# LAN9254_D_P2.net
KiCad netlist of a schematic drawn in Altium Designer
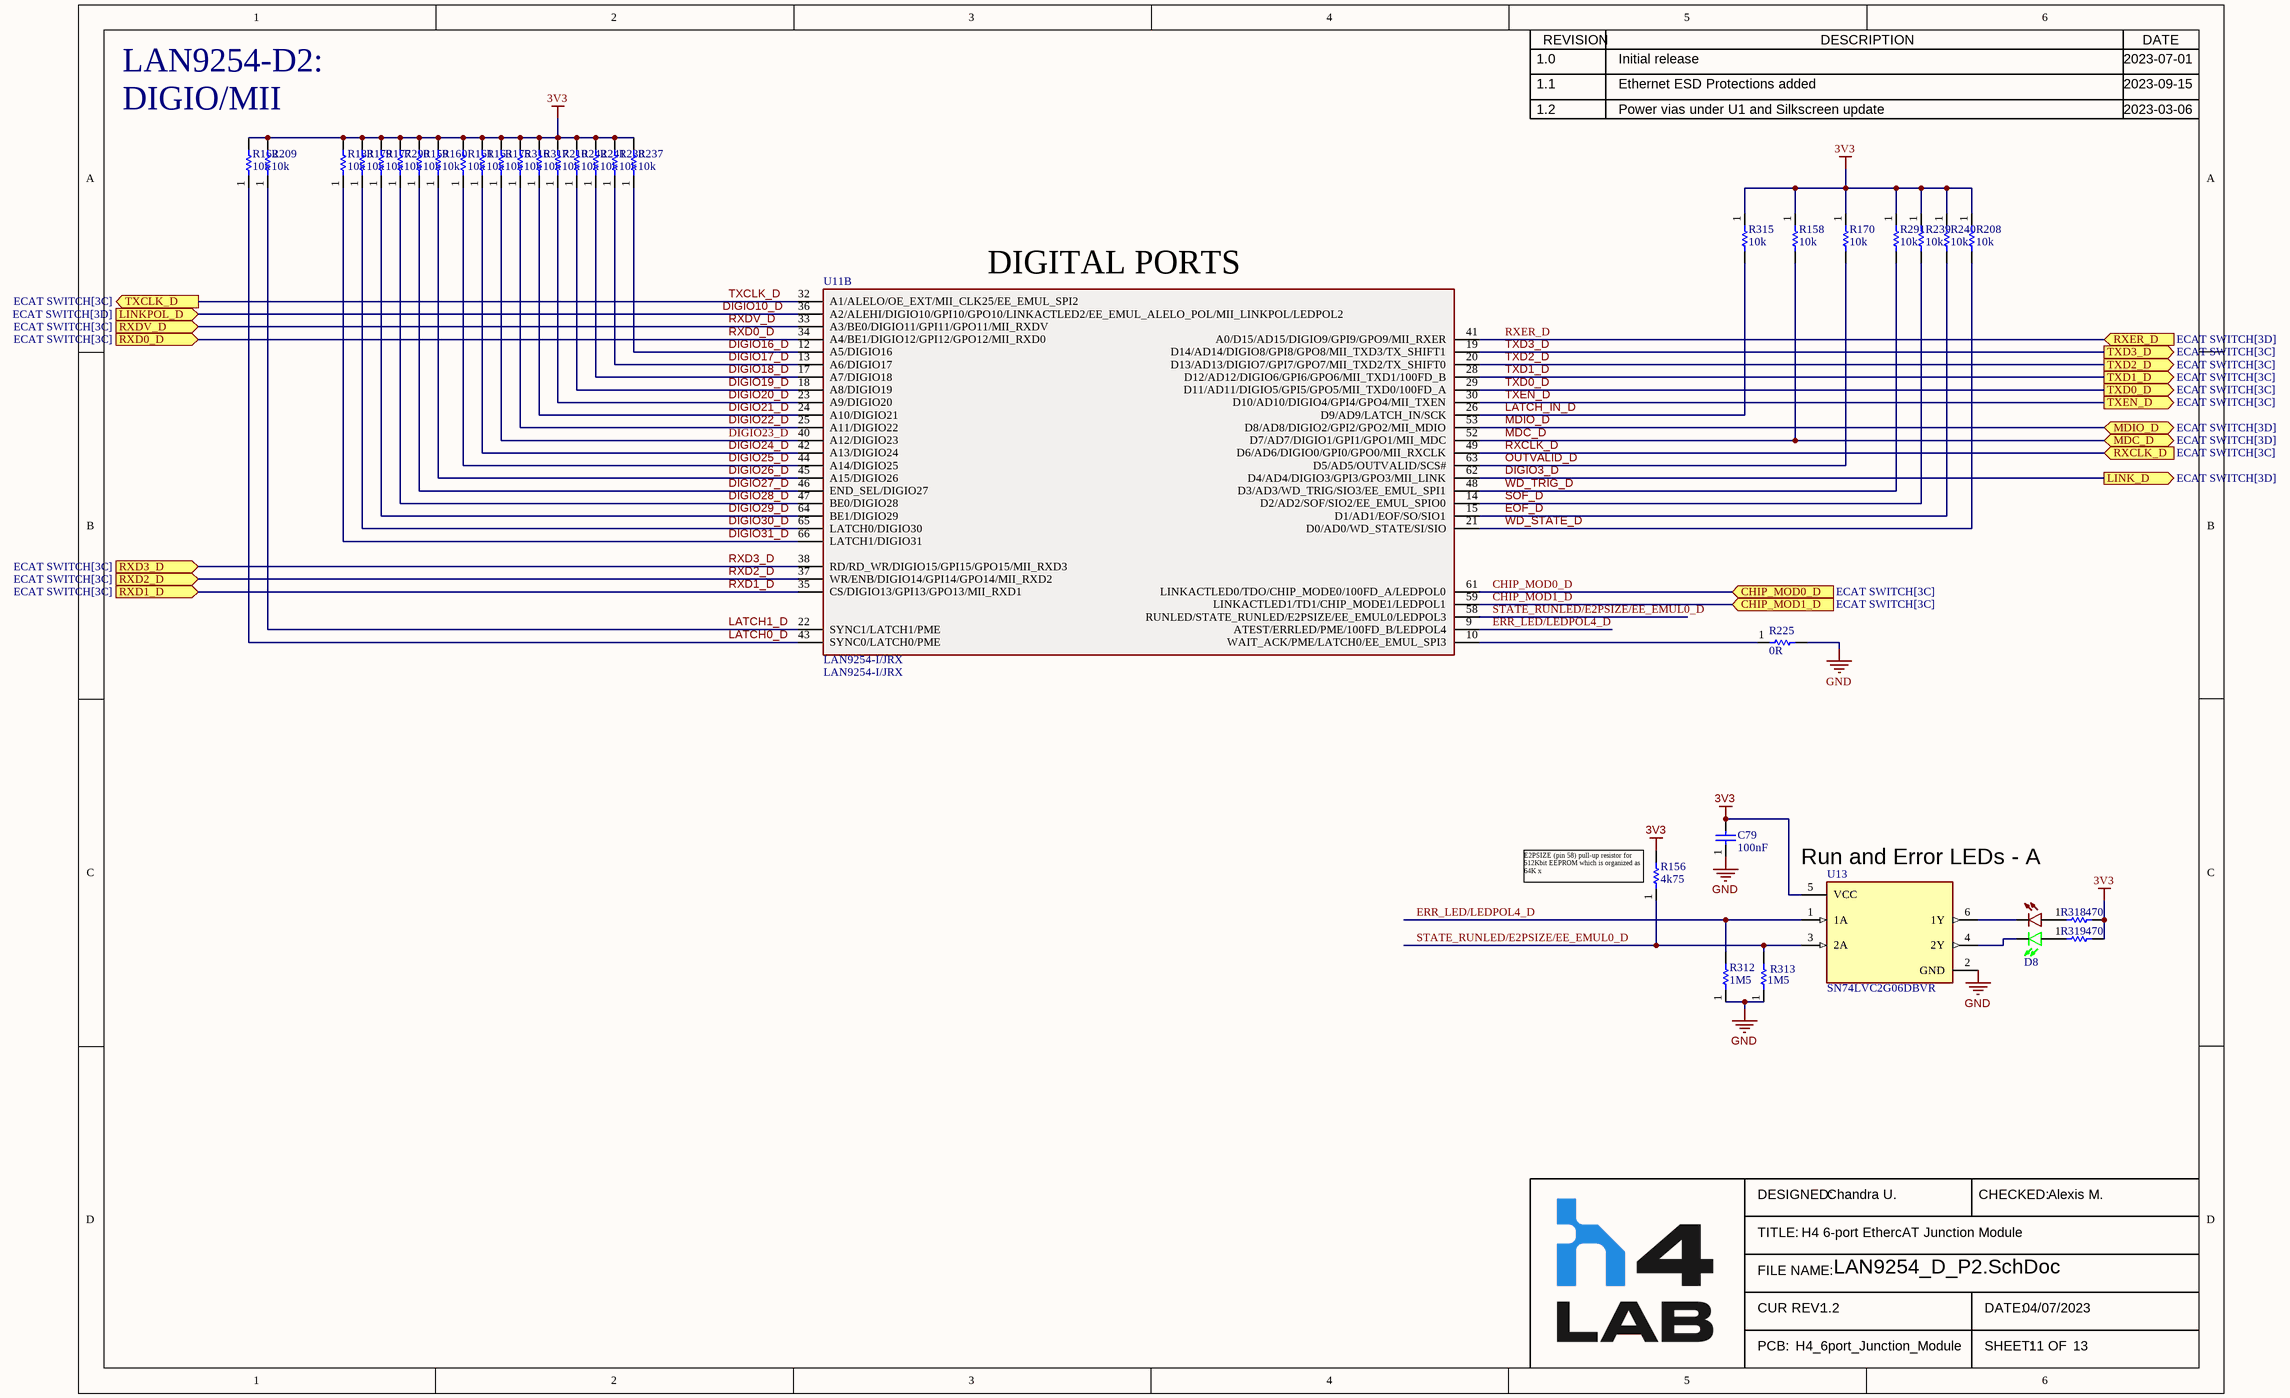
[diagram p0: LAN9254_D_P2.SchDoc]

(export (version "E")
  (design (tool "Eeschema 10.0.6"))
  (components
    (comp (ref "C79")
      (value "100nF")
      (footprint "CAPC1005X03N(0402)")
      (description "CAP CER 0.1UF 16V X7R 0402")
      (fields (field (name "MPN") "GRM155R71C104JA88D") (field (name "TOLERANCE") "5%"))
      (libsource (lib "IHMC_Altium_Lib") (part "100nF_16V_0402_CAP"))
    )
    (comp (ref "D8")
      (value "LTST-C195KGJRKT")
      (footprint "Dual_LED")
      (description "LED GREEN/RED CLEAR CHIP SMD")
      (libsource (lib "IHMC_Altium_Lib") (part "Green/Red_LED"))
    )
    (comp (ref "R156")
      (value "4k75")
      (footprint "RESC1005X06N(0402)")
      (description "RES SMD 4.75K OHM 1% 1/16W 0402")
      (fields (field (name "MPN") "RC0402FR-074K75L") (field (name "POWER") "1/16"))
      (libsource (lib "IHMC_Altium_Lib") (part "4k75_1/16_0402_RES"))
    )
    (comp (ref "R158")
      (value "10k")
      (footprint "RESC1005X06N(0402)")
      (description "RES SMD 10K OHM 1% 1/16W 0402")
      (fields (field (name "MPN") "RC0402FR-0710KL") (field (name "TOLERANCE") "1%"))
      (libsource (lib "IHMC_Resistors") (part "10k_1/16W_0402_RES"))
    )
    (comp (ref "R159")
      (value "10k")
      (footprint "RESC1005X06N(0402)")
      (description "RES SMD 10K OHM 1% 1/16W 0402")
      (fields (field (name "MPN") "RC0402FR-0710KL") (field (name "TOLERANCE") "1%"))
      (libsource (lib "IHMC_Resistors") (part "10k_1/16W_0402_RES"))
    )
    (comp (ref "R160")
      (value "10k")
      (footprint "RESC1005X06N(0402)")
      (description "RES SMD 10K OHM 1% 1/16W 0402")
      (fields (field (name "MPN") "RC0402FR-0710KL") (field (name "TOLERANCE") "1%"))
      (libsource (lib "IHMC_Resistors") (part "10k_1/16W_0402_RES"))
    )
    (comp (ref "R161")
      (value "10k")
      (footprint "RESC1005X06N(0402)")
      (description "RES SMD 10K OHM 1% 1/16W 0402")
      (fields (field (name "MPN") "RC0402FR-0710KL") (field (name "TOLERANCE") "1%"))
      (libsource (lib "IHMC_Resistors") (part "10k_1/16W_0402_RES"))
    )
    (comp (ref "R162")
      (value "10k")
      (footprint "RESC1005X06N(0402)")
      (description "RES SMD 10K OHM 1% 1/16W 0402")
      (fields (field (name "MPN") "RC0402FR-0710KL") (field (name "TOLERANCE") "1%"))
      (libsource (lib "IHMC_Resistors") (part "10k_1/16W_0402_RES"))
    )
    (comp (ref "R163")
      (value "10k")
      (footprint "RESC1005X06N(0402)")
      (description "RES SMD 10K OHM 1% 1/16W 0402")
      (fields (field (name "MPN") "RC0402FR-0710KL") (field (name "TOLERANCE") "1%"))
      (libsource (lib "IHMC_Resistors") (part "10k_1/16W_0402_RES"))
    )
    (comp (ref "R170")
      (value "10k")
      (footprint "RESC1005X06N(0402)")
      (description "RES SMD 10K OHM 1% 1/16W 0402")
      (fields (field (name "MPN") "RC0402FR-0710KL") (field (name "TOLERANCE") "1%"))
      (libsource (lib "IHMC_Resistors") (part "10k_1/16W_0402_RES"))
    )
    (comp (ref "R175")
      (value "10k")
      (footprint "RESC1005X06N(0402)")
      (description "RES SMD 10K OHM 1% 1/16W 0402")
      (fields (field (name "MPN") "RC0402FR-0710KL") (field (name "TOLERANCE") "1%"))
      (libsource (lib "IHMC_Resistors") (part "10k_1/16W_0402_RES"))
    )
    (comp (ref "R177")
      (value "10k")
      (footprint "RESC1005X06N(0402)")
      (description "RES SMD 10K OHM 1% 1/16W 0402")
      (fields (field (name "MPN") "RC0402FR-0710KL") (field (name "TOLERANCE") "1%"))
      (libsource (lib "IHMC_Resistors") (part "10k_1/16W_0402_RES"))
    )
    (comp (ref "R179")
      (value "10k")
      (footprint "RESC1005X06N(0402)")
      (description "RES SMD 10K OHM 1% 1/16W 0402")
      (fields (field (name "MPN") "RC0402FR-0710KL") (field (name "TOLERANCE") "1%"))
      (libsource (lib "IHMC_Resistors") (part "10k_1/16W_0402_RES"))
    )
    (comp (ref "R183")
      (value "10k")
      (footprint "RESC1005X06N(0402)")
      (description "RES SMD 10K OHM 1% 1/16W 0402")
      (fields (field (name "MPN") "RC0402FR-0710KL") (field (name "TOLERANCE") "1%"))
      (libsource (lib "IHMC_Resistors") (part "10k_1/16W_0402_RES"))
    )
    (comp (ref "R208")
      (value "10k")
      (footprint "RESC1005X06N(0402)")
      (description "RES SMD 10K OHM 1% 1/16W 0402")
      (fields (field (name "MPN") "RC0402FR-0710KL") (field (name "TOLERANCE") "1%"))
      (libsource (lib "IHMC_Resistors") (part "10k_1/16W_0402_RES"))
    )
    (comp (ref "R209")
      (value "10k")
      (footprint "RESC1005X06N(0402)")
      (description "RES SMD 10K OHM 1% 1/16W 0402")
      (fields (field (name "MPN") "RC0402FR-0710KL") (field (name "TOLERANCE") "1%"))
      (libsource (lib "IHMC_Resistors") (part "10k_1/16W_0402_RES"))
    )
    (comp (ref "R210")
      (value "10k")
      (footprint "RESC1005X06N(0402)")
      (description "RES SMD 10K OHM 1% 1/16W 0402")
      (fields (field (name "MPN") "RC0402FR-0710KL") (field (name "TOLERANCE") "1%"))
      (libsource (lib "IHMC_Resistors") (part "10k_1/16W_0402_RES"))
    )
    (comp (ref "R225")
      (value "0R")
      (footprint "0402")
      (fields
        (field (name "MANUFACTURER") "Vishay Dale")
        (field (name "MANUFACTURER PART NUMBER") "RCS04020000Z0ED")
      )
      (libsource (lib "IHMC_Altium_Lib") (part "0R_1/5W_0402_RCS04020000Z0ED_RES"))
    )
    (comp (ref "R237")
      (value "10k")
      (footprint "RESC1005X06N(0402)")
      (description "RES SMD 10K OHM 1% 1/16W 0402")
      (fields (field (name "MPN") "RC0402FR-0710KL") (field (name "TOLERANCE") "1%"))
      (libsource (lib "IHMC_Resistors") (part "10k_1/16W_0402_RES"))
    )
    (comp (ref "R238")
      (value "10k")
      (footprint "RESC1005X06N(0402)")
      (description "RES SMD 10K OHM 1% 1/16W 0402")
      (fields (field (name "MPN") "RC0402FR-0710KL") (field (name "TOLERANCE") "1%"))
      (libsource (lib "IHMC_Resistors") (part "10k_1/16W_0402_RES"))
    )
    (comp (ref "R239")
      (value "10k")
      (footprint "RESC1005X06N(0402)")
      (description "RES SMD 10K OHM 1% 1/16W 0402")
      (fields (field (name "MPN") "RC0402FR-0710KL") (field (name "TOLERANCE") "1%"))
      (libsource (lib "IHMC_Resistors") (part "10k_1/16W_0402_RES"))
    )
    (comp (ref "R240")
      (value "10k")
      (footprint "RESC1005X06N(0402)")
      (description "RES SMD 10K OHM 1% 1/16W 0402")
      (fields (field (name "MPN") "RC0402FR-0710KL") (field (name "TOLERANCE") "1%"))
      (libsource (lib "IHMC_Resistors") (part "10k_1/16W_0402_RES"))
    )
    (comp (ref "R241")
      (value "10k")
      (footprint "RESC1005X06N(0402)")
      (description "RES SMD 10K OHM 1% 1/16W 0402")
      (fields (field (name "MPN") "RC0402FR-0710KL") (field (name "TOLERANCE") "1%"))
      (libsource (lib "IHMC_Resistors") (part "10k_1/16W_0402_RES"))
    )
    (comp (ref "R242")
      (value "10k")
      (footprint "RESC1005X06N(0402)")
      (description "RES SMD 10K OHM 1% 1/16W 0402")
      (fields (field (name "MPN") "RC0402FR-0710KL") (field (name "TOLERANCE") "1%"))
      (libsource (lib "IHMC_Resistors") (part "10k_1/16W_0402_RES"))
    )
    (comp (ref "R290")
      (value "10k")
      (footprint "RESC1005X06N(0402)")
      (description "RES SMD 10K OHM 1% 1/16W 0402")
      (fields (field (name "MPN") "RC0402FR-0710KL") (field (name "TOLERANCE") "1%"))
      (libsource (lib "IHMC_Resistors") (part "10k_1/16W_0402_RES"))
    )
    (comp (ref "R291")
      (value "10k")
      (footprint "RESC1005X06N(0402)")
      (description "RES SMD 10K OHM 1% 1/16W 0402")
      (fields (field (name "MPN") "RC0402FR-0710KL") (field (name "TOLERANCE") "1%"))
      (libsource (lib "IHMC_Resistors") (part "10k_1/16W_0402_RES"))
    )
    (comp (ref "R312")
      (value "1M5")
      (footprint "0402")
      (description "RES SMD 1.5M OHM 5% 1/16W 0402")
      (fields
        (field (name "MANUFACTURER") "Vishay Dale")
        (field (name "MANUFACTURER PART NUMBER") "CRCW04021M50JNED")
      )
      (libsource (lib "IHMC_Altium_Lib") (part "1M5_1/16W_0402_CRCW04021M50JNED_RES"))
    )
    (comp (ref "R313")
      (value "1M5")
      (footprint "0402")
      (description "RES SMD 1.5M OHM 5% 1/16W 0402")
      (fields
        (field (name "MANUFACTURER") "Vishay Dale")
        (field (name "MANUFACTURER PART NUMBER") "CRCW04021M50JNED")
      )
      (libsource (lib "IHMC_Altium_Lib") (part "1M5_1/16W_0402_CRCW04021M50JNED_RES"))
    )
    (comp (ref "R315")
      (value "10k")
      (footprint "RESC1005X06N(0402)")
      (description "RES SMD 10K OHM 1% 1/16W 0402")
      (fields (field (name "MPN") "RC0402FR-0710KL") (field (name "TOLERANCE") "1%"))
      (libsource (lib "IHMC_Resistors") (part "10k_1/16W_0402_RES"))
    )
    (comp (ref "R316")
      (value "10k")
      (footprint "RESC1005X06N(0402)")
      (description "RES SMD 10K OHM 1% 1/16W 0402")
      (fields (field (name "MPN") "RC0402FR-0710KL") (field (name "TOLERANCE") "1%"))
      (libsource (lib "IHMC_Resistors") (part "10k_1/16W_0402_RES"))
    )
    (comp (ref "R317")
      (value "10k")
      (footprint "RESC1005X06N(0402)")
      (description "RES SMD 10K OHM 1% 1/16W 0402")
      (fields (field (name "MPN") "RC0402FR-0710KL") (field (name "TOLERANCE") "1%"))
      (libsource (lib "IHMC_Resistors") (part "10k_1/16W_0402_RES"))
    )
    (comp (ref "R318")
      (value "470")
      (footprint "0402")
      (description "Vishay CRCW Series Thick Film Resistor 0402 Case 470 5% 0.063W 200ppm/K")
      (fields
        (field (name "MANUFACTURER") "Vishay Dale")
        (field (name "MANUFACTURER PART NUMBER") "CRCW0402470RJNED")
      )
      (libsource (lib "IHMC_Altium_Lib") (part "470_1/10W_0402_CRCW0402470RJNED"))
    )
    (comp (ref "R319")
      (value "470")
      (footprint "0402")
      (description "Vishay CRCW Series Thick Film Resistor 0402 Case 470 5% 0.063W 200ppm/K")
      (fields
        (field (name "MANUFACTURER") "Vishay Dale")
        (field (name "MANUFACTURER PART NUMBER") "CRCW0402470RJNED")
      )
      (libsource (lib "IHMC_Altium_Lib") (part "470_1/10W_0402_CRCW0402470RJNED"))
    )
    (comp (ref "U11")
      (value "LAN9254-I/JRX")
      (footprint "QFP50P1400X1400X120-81N")
      (description "2/3-PORT Ethercat Slave Controller With 32 Digios With Integrated Ethernet Phys")
      (fields (field (name "MANUFACTURER") "Microchip"))
      (libsource (lib "IHMC_Ethernet") (part "LAN9254-I/JRX"))
    )
    (comp (ref "U13")
      (value "SN74LVC2G06DBVR")
      (footprint "FP-DBV0006A-IPC_C")
      (description "Buffer/Driver 2-CH Inverting Open Drain CMOS 6-Pin SOT-23 T/R")
      (fields (field (name "MANUFACTURER") "Texas Instruments"))
      (libsource (lib "IHMC_Altium_Lib") (part "BUF_dual_SN74LVC2G06DBVR"))
    )
  )
  (nets
    (net (code "1") (name "/CHIP_MOD0_D") (class "Default")
      (node (ref "U11") (pin "61") (pinfunction "LINKACTLED0/TDO/CHIP_MODE0/100FD_A/LEDPOL0_61") (pintype "passive"))
    )
    (net (code "2") (name "/CHIP_MOD1_D") (class "Default")
      (node (ref "U11") (pin "59") (pinfunction "LINKACTLED1/TD1/CHIP_MODE1/LEDPOL1_59") (pintype "passive"))
    )
    (net (code "3") (name "/DIGIO3_D") (class "Default")
      (node (ref "U11") (pin "62") (pinfunction "D4/AD4/DIGIO3/GPI3/GPO3/MII_LINK_62") (pintype "passive"))
    )
    (net (code "4") (name "/DIGIO10_D") (class "Default")
      (node (ref "U11") (pin "36") (pinfunction "A2/ALEHI/DIGIO10/GPI10/GPO10/LINKACTLED2/EE_EMUL_ALELO_POL/MII_LINKPOL/LEDPOL2_36") (pintype "passive"))
    )
    (net (code "5") (name "/DIGIO16_D") (class "Default")
      (node (ref "R237") (pin "1") (pinfunction "1_1") (pintype "passive"))
      (node (ref "U11") (pin "12") (pinfunction "A5/DIGIO16_12") (pintype "passive"))
    )
    (net (code "6") (name "/DIGIO17_D") (class "Default")
      (node (ref "R238") (pin "1") (pinfunction "1_1") (pintype "passive"))
      (node (ref "U11") (pin "13") (pinfunction "A6/DIGIO17_13") (pintype "passive"))
    )
    (net (code "7") (name "/DIGIO18_D") (class "Default")
      (node (ref "R241") (pin "1") (pinfunction "1_1") (pintype "passive"))
      (node (ref "U11") (pin "17") (pinfunction "A7/DIGIO18_17") (pintype "passive"))
    )
    (net (code "8") (name "/DIGIO19_D") (class "Default")
      (node (ref "R242") (pin "1") (pinfunction "1_1") (pintype "passive"))
      (node (ref "U11") (pin "18") (pinfunction "A8/DIGIO19_18") (pintype "passive"))
    )
    (net (code "9") (name "/DIGIO20_D") (class "Default")
      (node (ref "R210") (pin "1") (pinfunction "1_1") (pintype "passive"))
      (node (ref "U11") (pin "23") (pinfunction "A9/DIGIO20_23") (pintype "passive"))
    )
    (net (code "10") (name "/DIGIO21_D") (class "Default")
      (node (ref "R317") (pin "1") (pinfunction "1_1") (pintype "passive"))
      (node (ref "U11") (pin "24") (pinfunction "A10/DIGIO21_24") (pintype "passive"))
    )
    (net (code "11") (name "/DIGIO22_D") (class "Default")
      (node (ref "R316") (pin "1") (pinfunction "1_1") (pintype "passive"))
      (node (ref "U11") (pin "25") (pinfunction "A11/DIGIO22_25") (pintype "passive"))
    )
    (net (code "12") (name "/DIGIO23_D") (class "Default")
      (node (ref "R175") (pin "1") (pinfunction "1_1") (pintype "passive"))
      (node (ref "U11") (pin "40") (pinfunction "A12/DIGIO23_40") (pintype "passive"))
    )
    (net (code "13") (name "/DIGIO24_D") (class "Default")
      (node (ref "R163") (pin "1") (pinfunction "1_1") (pintype "passive"))
      (node (ref "U11") (pin "42") (pinfunction "A13/DIGIO24_42") (pintype "passive"))
    )
    (net (code "14") (name "/DIGIO25_D") (class "Default")
      (node (ref "R161") (pin "1") (pinfunction "1_1") (pintype "passive"))
      (node (ref "U11") (pin "44") (pinfunction "A14/DIGIO25_44") (pintype "passive"))
    )
    (net (code "15") (name "/DIGIO26_D") (class "Default")
      (node (ref "R160") (pin "1") (pinfunction "1_1") (pintype "passive"))
      (node (ref "U11") (pin "45") (pinfunction "A15/DIGIO26_45") (pintype "passive"))
    )
    (net (code "16") (name "/DIGIO27_D") (class "Default")
      (node (ref "R159") (pin "1") (pinfunction "1_1") (pintype "passive"))
      (node (ref "U11") (pin "46") (pinfunction "END_SEL/DIGIO27_46") (pintype "passive"))
    )
    (net (code "17") (name "/DIGIO28_D") (class "Default")
      (node (ref "R290") (pin "1") (pinfunction "1_1") (pintype "passive"))
      (node (ref "U11") (pin "47") (pinfunction "BE0/DIGIO28_47") (pintype "passive"))
    )
    (net (code "18") (name "/DIGIO29_D") (class "Default")
      (node (ref "R177") (pin "1") (pinfunction "1_1") (pintype "passive"))
      (node (ref "U11") (pin "64") (pinfunction "BE1/DIGIO29_64") (pintype "passive"))
    )
    (net (code "19") (name "/DIGIO30_D") (class "Default")
      (node (ref "R179") (pin "1") (pinfunction "1_1") (pintype "passive"))
      (node (ref "U11") (pin "65") (pinfunction "LATCH0/DIGIO30_65") (pintype "passive"))
    )
    (net (code "20") (name "/DIGIO31_D") (class "Default")
      (node (ref "R183") (pin "1") (pinfunction "1_1") (pintype "passive"))
      (node (ref "U11") (pin "66") (pinfunction "LATCH1/DIGIO31_66") (pintype "passive"))
    )
    (net (code "21") (name "/EOF_D") (class "Default")
      (node (ref "R240") (pin "2") (pinfunction "2_2") (pintype "passive"))
      (node (ref "U11") (pin "15") (pinfunction "D1/AD1/EOF/SO/SIO1_15") (pintype "passive"))
    )
    (net (code "22") (name "/ERR_LED{slash}LEDPOL4_D") (class "Default")
      (node (ref "R312") (pin "2") (pinfunction "2_2") (pintype "passive"))
      (node (ref "U11") (pin "9") (pinfunction "ATEST/ERRLED/PME/100FD_B/LEDPOL4_9") (pintype "passive"))
      (node (ref "U13") (pin "1") (pinfunction "1A_1") (pintype "input"))
    )
    (net (code "23") (name "/LATCH0_D") (class "Default")
      (node (ref "R162") (pin "1") (pinfunction "1_1") (pintype "passive"))
      (node (ref "U11") (pin "43") (pinfunction "SYNC0/LATCH0/PME_43") (pintype "passive"))
    )
    (net (code "24") (name "/LATCH1_D") (class "Default")
      (node (ref "R209") (pin "1") (pinfunction "1_1") (pintype "passive"))
      (node (ref "U11") (pin "22") (pinfunction "SYNC1/LATCH1/PME_22") (pintype "passive"))
    )
    (net (code "25") (name "/LATCH_IN_D") (class "Default")
      (node (ref "R315") (pin "2") (pinfunction "2_2") (pintype "passive"))
      (node (ref "U11") (pin "26") (pinfunction "D9/AD9/LATCH_IN/SCK_26") (pintype "passive"))
    )
    (net (code "26") (name "/MDC_D") (class "Default")
      (node (ref "R158") (pin "2") (pinfunction "2_2") (pintype "passive"))
      (node (ref "U11") (pin "52") (pinfunction "D7/AD7/DIGIO1/GPI1/GPO1/MII_MDC_52") (pintype "passive"))
    )
    (net (code "27") (name "/MDIO_D") (class "Default")
      (node (ref "U11") (pin "53") (pinfunction "D8/AD8/DIGIO2/GPI2/GPO2/MII_MDIO_53") (pintype "passive"))
    )
    (net (code "28") (name "/OUTVALID_D") (class "Default")
      (node (ref "R170") (pin "2") (pinfunction "2_2") (pintype "passive"))
      (node (ref "U11") (pin "63") (pinfunction "D5/AD5/OUTVALID/SCS#_63") (pintype "passive"))
    )
    (net (code "29") (name "/RXCLK_D") (class "Default")
      (node (ref "U11") (pin "49") (pinfunction "D6/AD6/DIGIO0/GPI0/GPO0/MII_RXCLK_49") (pintype "passive"))
    )
    (net (code "30") (name "/RXD0_D") (class "Default")
      (node (ref "U11") (pin "34") (pinfunction "A4/BE1/DIGIO12/GPI12/GPO12/MII_RXD0_34") (pintype "passive"))
    )
    (net (code "31") (name "/RXD1_D") (class "Default")
      (node (ref "U11") (pin "35") (pinfunction "CS/DIGIO13/GPI13/GPO13/MII_RXD1_35") (pintype "passive"))
    )
    (net (code "32") (name "/RXD2_D") (class "Default")
      (node (ref "U11") (pin "37") (pinfunction "WR/ENB/DIGIO14/GPI14/GPO14/MII_RXD2_37") (pintype "passive"))
    )
    (net (code "33") (name "/RXD3_D") (class "Default")
      (node (ref "U11") (pin "38") (pinfunction "RD/RD_WR/DIGIO15/GPI15/GPO15/MII_RXD3_38") (pintype "passive"))
    )
    (net (code "34") (name "/RXDV_D") (class "Default")
      (node (ref "U11") (pin "33") (pinfunction "A3/BE0/DIGIO11/GPI11/GPO11/MII_RXDV_33") (pintype "passive"))
    )
    (net (code "35") (name "/RXER_D") (class "Default")
      (node (ref "U11") (pin "41") (pinfunction "A0/D15/AD15/DIGIO9/GPI9/GPO9/MII_RXER_41") (pintype "passive"))
    )
    (net (code "36") (name "/SOF_D") (class "Default")
      (node (ref "R239") (pin "2") (pinfunction "2_2") (pintype "passive"))
      (node (ref "U11") (pin "14") (pinfunction "D2/AD2/SOF/SIO2/EE_EMUL_SPIO0_14") (pintype "passive"))
    )
    (net (code "37") (name "/STATE_RUNLED{slash}E2PSIZE{slash}EE_EMUL0_D") (class "Default")
      (node (ref "R156") (pin "1") (pinfunction "1_1") (pintype "passive"))
      (node (ref "R313") (pin "2") (pinfunction "2_2") (pintype "passive"))
      (node (ref "U11") (pin "58") (pinfunction "RUNLED/STATE_RUNLED/E2PSIZE/EE_EMUL0/LEDPOL3_58") (pintype "passive"))
      (node (ref "U13") (pin "3") (pinfunction "2A_3") (pintype "input"))
    )
    (net (code "38") (name "/TXCLK_D") (class "Default")
      (node (ref "U11") (pin "32") (pinfunction "A1/ALELO/OE_EXT/MII_CLK25/EE_EMUL_SPI2_32") (pintype "passive"))
    )
    (net (code "39") (name "/TXD0_D") (class "Default")
      (node (ref "U11") (pin "29") (pinfunction "D11/AD11/DIGIO5/GPI5/GPO5/MII_TXD0/100FD_A_29") (pintype "passive"))
    )
    (net (code "40") (name "/TXD1_D") (class "Default")
      (node (ref "U11") (pin "28") (pinfunction "D12/AD12/DIGIO6/GPI6/GPO6/MII_TXD1/100FD_B_28") (pintype "passive"))
    )
    (net (code "41") (name "/TXD2_D") (class "Default")
      (node (ref "U11") (pin "20") (pinfunction "D13/AD13/DIGIO7/GPI7/GPO7/MII_TXD2/TX_SHIFT0_20") (pintype "passive"))
    )
    (net (code "42") (name "/TXD3_D") (class "Default")
      (node (ref "U11") (pin "19") (pinfunction "D14/AD14/DIGIO8/GPI8/GPO8/MII_TXD3/TX_SHIFT1_19") (pintype "passive"))
    )
    (net (code "43") (name "/TXEN_D") (class "Default")
      (node (ref "U11") (pin "30") (pinfunction "D10/AD10/DIGIO4/GPI4/GPO4/MII_TXEN_30") (pintype "passive"))
    )
    (net (code "44") (name "/WD_STATE_D") (class "Default")
      (node (ref "R208") (pin "2") (pinfunction "2_2") (pintype "passive"))
      (node (ref "U11") (pin "21") (pinfunction "D0/AD0/WD_STATE/SI/SIO_21") (pintype "passive"))
    )
    (net (code "45") (name "/WD_TRIG_D") (class "Default")
      (node (ref "R291") (pin "2") (pinfunction "2_2") (pintype "passive"))
      (node (ref "U11") (pin "48") (pinfunction "D3/AD3/WD_TRIG/SIO3/EE_EMUL_SPI1_48") (pintype "passive"))
    )
    (net (code "46") (name "3V3") (class "Default")
      (node (ref "C79") (pin "2") (pinfunction "2_2") (pintype "passive"))
      (node (ref "R156") (pin "2") (pinfunction "2_2") (pintype "passive"))
      (node (ref "R158") (pin "1") (pinfunction "1_1") (pintype "passive"))
      (node (ref "R159") (pin "2") (pinfunction "2_2") (pintype "passive"))
      (node (ref "R160") (pin "2") (pinfunction "2_2") (pintype "passive"))
      (node (ref "R161") (pin "2") (pinfunction "2_2") (pintype "passive"))
      (node (ref "R162") (pin "2") (pinfunction "2_2") (pintype "passive"))
      (node (ref "R163") (pin "2") (pinfunction "2_2") (pintype "passive"))
      (node (ref "R170") (pin "1") (pinfunction "1_1") (pintype "passive"))
      (node (ref "R175") (pin "2") (pinfunction "2_2") (pintype "passive"))
      (node (ref "R177") (pin "2") (pinfunction "2_2") (pintype "passive"))
      (node (ref "R179") (pin "2") (pinfunction "2_2") (pintype "passive"))
      (node (ref "R183") (pin "2") (pinfunction "2_2") (pintype "passive"))
      (node (ref "R208") (pin "1") (pinfunction "1_1") (pintype "passive"))
      (node (ref "R209") (pin "2") (pinfunction "2_2") (pintype "passive"))
      (node (ref "R210") (pin "2") (pinfunction "2_2") (pintype "passive"))
      (node (ref "R237") (pin "2") (pinfunction "2_2") (pintype "passive"))
      (node (ref "R238") (pin "2") (pinfunction "2_2") (pintype "passive"))
      (node (ref "R239") (pin "1") (pinfunction "1_1") (pintype "passive"))
      (node (ref "R240") (pin "1") (pinfunction "1_1") (pintype "passive"))
      (node (ref "R241") (pin "2") (pinfunction "2_2") (pintype "passive"))
      (node (ref "R242") (pin "2") (pinfunction "2_2") (pintype "passive"))
      (node (ref "R290") (pin "2") (pinfunction "2_2") (pintype "passive"))
      (node (ref "R291") (pin "1") (pinfunction "1_1") (pintype "passive"))
      (node (ref "R315") (pin "1") (pinfunction "1_1") (pintype "passive"))
      (node (ref "R316") (pin "2") (pinfunction "2_2") (pintype "passive"))
      (node (ref "R317") (pin "2") (pinfunction "2_2") (pintype "passive"))
      (node (ref "R318") (pin "2") (pinfunction "2_2") (pintype "passive"))
      (node (ref "R319") (pin "2") (pinfunction "2_2") (pintype "passive"))
      (node (ref "U13") (pin "5") (pinfunction "VCC_5") (pintype "power_in"))
    )
    (net (code "47") (name "GND") (class "Default")
      (node (ref "C79") (pin "1") (pinfunction "1_1") (pintype "passive"))
      (node (ref "R225") (pin "2") (pinfunction "2_2") (pintype "passive"))
      (node (ref "R312") (pin "1") (pinfunction "1_1") (pintype "passive"))
      (node (ref "R313") (pin "1") (pinfunction "1_1") (pintype "passive"))
      (node (ref "U13") (pin "2") (pinfunction "GND_2") (pintype "power_in"))
    )
    (net (code "48") (name "Net-(D8-Pad1)") (class "Default")
      (node (ref "D8") (pin "1") (pinfunction "1_1") (pintype "passive"))
      (node (ref "R319") (pin "1") (pinfunction "1_1") (pintype "passive"))
    )
    (net (code "49") (name "Net-(D8-Pad2)") (class "Default")
      (node (ref "D8") (pin "2") (pinfunction "2_2") (pintype "passive"))
      (node (ref "R318") (pin "1") (pinfunction "1_1") (pintype "passive"))
    )
    (net (code "50") (name "Net-(U11B-WAIT_ACK{slash}PME{slash}LATCH0{slash}EE_EMUL_SPI3)") (class "Default")
      (node (ref "R225") (pin "1") (pinfunction "1_1") (pintype "passive"))
      (node (ref "U11") (pin "10") (pinfunction "WAIT_ACK/PME/LATCH0/EE_EMUL_SPI3_10") (pintype "passive"))
    )
    (net (code "51") (name "Net-(U13-1Y)") (class "Default")
      (node (ref "D8") (pin "4") (pinfunction "4_4") (pintype "passive"))
      (node (ref "U13") (pin "6") (pinfunction "1Y_6") (pintype "output"))
    )
    (net (code "52") (name "Net-(U13-2Y)") (class "Default")
      (node (ref "D8") (pin "3") (pinfunction "3_3") (pintype "passive"))
      (node (ref "U13") (pin "4") (pinfunction "2Y_4") (pintype "output"))
    )
  )
)
